# power_board.net
KiCad netlist of a schematic drawn in EAGLE
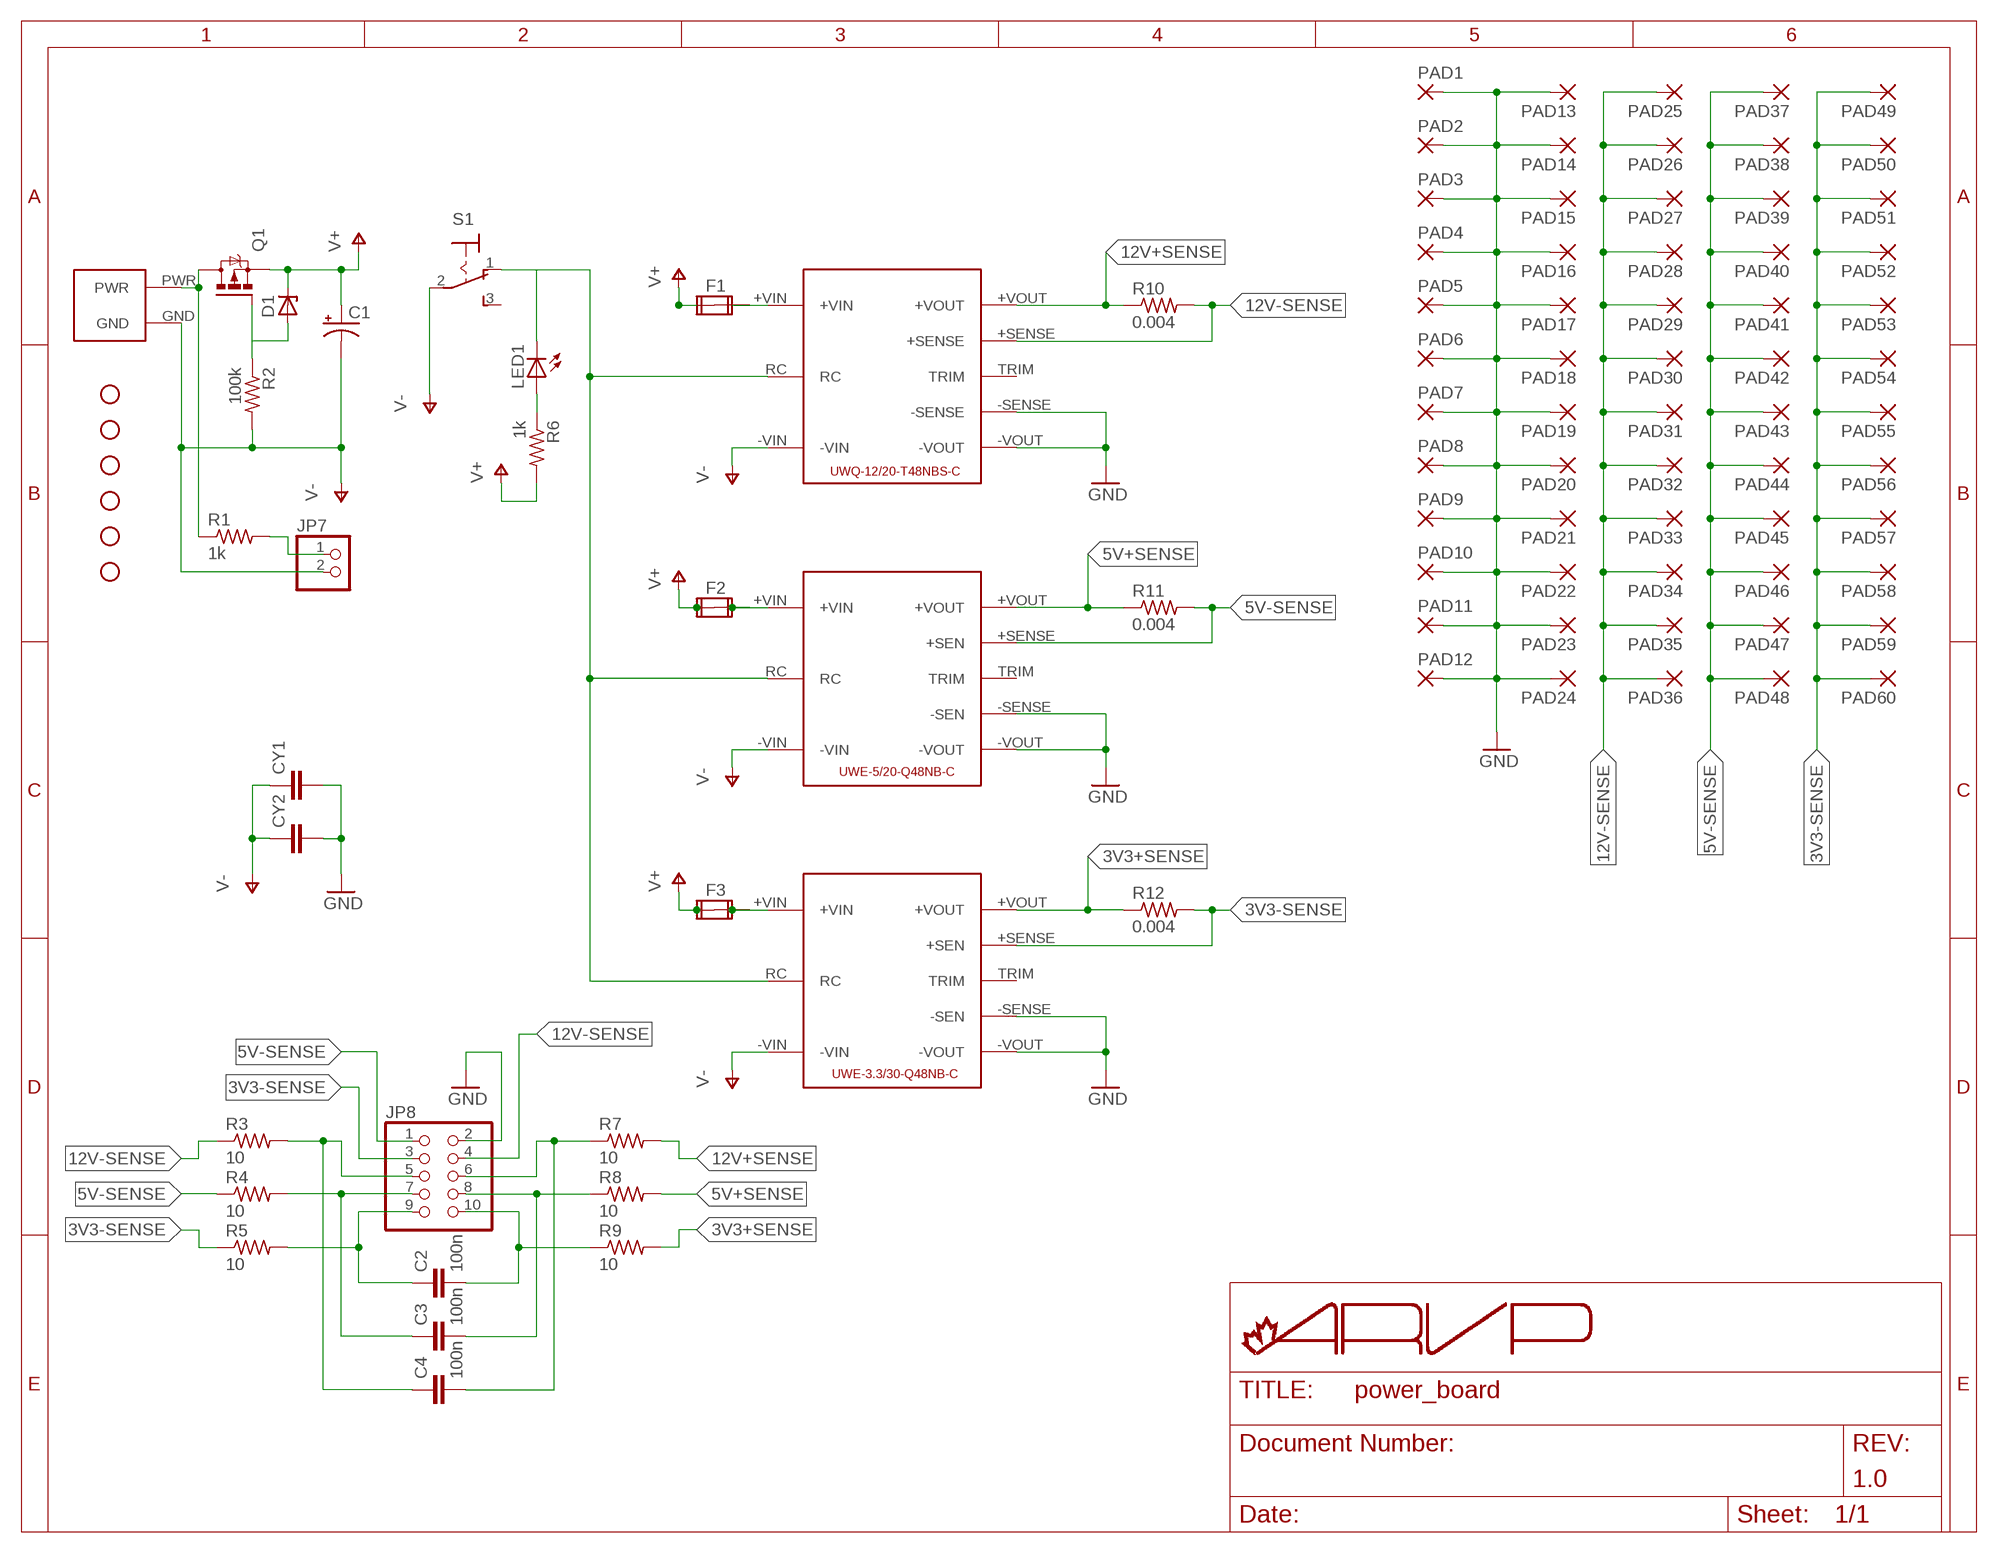
[diagram p0: schematic, sheet 1]

(export (version "E")
  (design (tool "Eeschema 10.0.6"))
  (components
    (comp (ref "C1")
      (value "CPOL-USE5-10.5")
      (footprint "eagle-import:E5-10,5")
      (libsource (lib "eagle-import") (part "CPOL-USE5-10.5"))
    )
    (comp (ref "C2")
      (value "100n")
      (footprint "eagle-import:C025-024X044")
      (libsource (lib "eagle-import") (part "C-EU025-024X044"))
    )
    (comp (ref "C3")
      (value "100n")
      (footprint "eagle-import:C025-024X044")
      (libsource (lib "eagle-import") (part "C-EU025-024X044"))
    )
    (comp (ref "C4")
      (value "100n")
      (footprint "eagle-import:C025-024X044")
      (libsource (lib "eagle-import") (part "C-EU025-024X044"))
    )
    (comp (ref "CY1")
      (value "CYYC7B5")
      (footprint "eagle-import:YC7B5")
      (libsource (lib "eagle-import") (part "CYYC7B5"))
    )
    (comp (ref "CY2")
      (value "CYYC7B5")
      (footprint "eagle-import:YC7B5")
      (libsource (lib "eagle-import") (part "CYYC7B5"))
    )
    (comp (ref "D1")
      (value "ZENER-DIODEDO35Z10")
      (footprint "eagle-import:DO35Z10")
      (libsource (lib "eagle-import") (part "ZENER-DIODEDO35Z10"))
    )
    (comp (ref "F1")
      (value "FUSE2P")
      (footprint "eagle-import:FUSE1")
      (libsource (lib "eagle-import") (part "FUSE2P"))
    )
    (comp (ref "F2")
      (value "FUSE2P")
      (footprint "eagle-import:FUSE1")
      (libsource (lib "eagle-import") (part "FUSE2P"))
    )
    (comp (ref "F3")
      (value "FUSE2P")
      (footprint "eagle-import:FUSE1")
      (libsource (lib "eagle-import") (part "FUSE2P"))
    )
    (comp (ref "JP1")
      (value "STAND-OFF")
      (footprint "eagle-import:STAND-OFF")
      (libsource (lib "eagle-import") (part "STAND-OFF"))
    )
    (comp (ref "JP2")
      (value "STAND-OFF")
      (footprint "eagle-import:STAND-OFF")
      (libsource (lib "eagle-import") (part "STAND-OFF"))
    )
    (comp (ref "JP3")
      (value "STAND-OFF")
      (footprint "eagle-import:STAND-OFF")
      (libsource (lib "eagle-import") (part "STAND-OFF"))
    )
    (comp (ref "JP4")
      (value "STAND-OFF")
      (footprint "eagle-import:STAND-OFF")
      (libsource (lib "eagle-import") (part "STAND-OFF"))
    )
    (comp (ref "JP5")
      (value "STAND-OFF")
      (footprint "eagle-import:STAND-OFF")
      (libsource (lib "eagle-import") (part "STAND-OFF"))
    )
    (comp (ref "JP6")
      (value "STAND-OFF")
      (footprint "eagle-import:STAND-OFF")
      (libsource (lib "eagle-import") (part "STAND-OFF"))
    )
    (comp (ref "JP7")
      (value "PINHD-1X2")
      (footprint "eagle-import:1X02")
      (libsource (lib "eagle-import") (part "PINHD-1X2"))
    )
    (comp (ref "JP8")
      (value "PINHD-2X5")
      (footprint "eagle-import:2X05")
      (libsource (lib "eagle-import") (part "PINHD-2X5"))
    )
    (comp (ref "LED1")
      (value "LED3MM")
      (footprint "eagle-import:LED3MM")
      (libsource (lib "eagle-import") (part "LED3MM"))
    )
    (comp (ref "P$1")
      (value "AND_PWR")
      (footprint "eagle-import:AND_PWR")
      (libsource (lib "eagle-import") (part "AND_PWR"))
    )
    (comp (ref "PAD1")
      (value "WIREPAD3,17/1,3")
      (footprint "eagle-import:3,17_1,3")
      (libsource (lib "eagle-import") (part "WIREPAD3,17/1,3"))
    )
    (comp (ref "PAD2")
      (value "WIREPAD3,17/1,3")
      (footprint "eagle-import:3,17_1,3")
      (libsource (lib "eagle-import") (part "WIREPAD3,17/1,3"))
    )
    (comp (ref "PAD3")
      (value "WIREPAD3,17/1,3")
      (footprint "eagle-import:3,17_1,3")
      (libsource (lib "eagle-import") (part "WIREPAD3,17/1,3"))
    )
    (comp (ref "PAD4")
      (value "WIREPAD3,17/1,3")
      (footprint "eagle-import:3,17_1,3")
      (libsource (lib "eagle-import") (part "WIREPAD3,17/1,3"))
    )
    (comp (ref "PAD5")
      (value "WIREPAD3,17/1,3")
      (footprint "eagle-import:3,17_1,3")
      (libsource (lib "eagle-import") (part "WIREPAD3,17/1,3"))
    )
    (comp (ref "PAD6")
      (value "WIREPAD3,17/1,3")
      (footprint "eagle-import:3,17_1,3")
      (libsource (lib "eagle-import") (part "WIREPAD3,17/1,3"))
    )
    (comp (ref "PAD7")
      (value "WIREPAD3,17/1,3")
      (footprint "eagle-import:3,17_1,3")
      (libsource (lib "eagle-import") (part "WIREPAD3,17/1,3"))
    )
    (comp (ref "PAD8")
      (value "WIREPAD3,17/1,3")
      (footprint "eagle-import:3,17_1,3")
      (libsource (lib "eagle-import") (part "WIREPAD3,17/1,3"))
    )
    (comp (ref "PAD9")
      (value "WIREPAD3,17/1,3")
      (footprint "eagle-import:3,17_1,3")
      (libsource (lib "eagle-import") (part "WIREPAD3,17/1,3"))
    )
    (comp (ref "PAD10")
      (value "WIREPAD3,17/1,3")
      (footprint "eagle-import:3,17_1,3")
      (libsource (lib "eagle-import") (part "WIREPAD3,17/1,3"))
    )
    (comp (ref "PAD11")
      (value "WIREPAD3,17/1,3")
      (footprint "eagle-import:3,17_1,3")
      (libsource (lib "eagle-import") (part "WIREPAD3,17/1,3"))
    )
    (comp (ref "PAD12")
      (value "WIREPAD3,17/1,3")
      (footprint "eagle-import:3,17_1,3")
      (libsource (lib "eagle-import") (part "WIREPAD3,17/1,3"))
    )
    (comp (ref "PAD13")
      (value "WIREPAD3,17/1,3")
      (footprint "eagle-import:3,17_1,3")
      (libsource (lib "eagle-import") (part "WIREPAD3,17/1,3"))
    )
    (comp (ref "PAD14")
      (value "WIREPAD3,17/1,3")
      (footprint "eagle-import:3,17_1,3")
      (libsource (lib "eagle-import") (part "WIREPAD3,17/1,3"))
    )
    (comp (ref "PAD15")
      (value "WIREPAD3,17/1,3")
      (footprint "eagle-import:3,17_1,3")
      (libsource (lib "eagle-import") (part "WIREPAD3,17/1,3"))
    )
    (comp (ref "PAD16")
      (value "WIREPAD3,17/1,3")
      (footprint "eagle-import:3,17_1,3")
      (libsource (lib "eagle-import") (part "WIREPAD3,17/1,3"))
    )
    (comp (ref "PAD17")
      (value "WIREPAD3,17/1,3")
      (footprint "eagle-import:3,17_1,3")
      (libsource (lib "eagle-import") (part "WIREPAD3,17/1,3"))
    )
    (comp (ref "PAD18")
      (value "WIREPAD3,17/1,3")
      (footprint "eagle-import:3,17_1,3")
      (libsource (lib "eagle-import") (part "WIREPAD3,17/1,3"))
    )
    (comp (ref "PAD19")
      (value "WIREPAD3,17/1,3")
      (footprint "eagle-import:3,17_1,3")
      (libsource (lib "eagle-import") (part "WIREPAD3,17/1,3"))
    )
    (comp (ref "PAD20")
      (value "WIREPAD3,17/1,3")
      (footprint "eagle-import:3,17_1,3")
      (libsource (lib "eagle-import") (part "WIREPAD3,17/1,3"))
    )
    (comp (ref "PAD21")
      (value "WIREPAD3,17/1,3")
      (footprint "eagle-import:3,17_1,3")
      (libsource (lib "eagle-import") (part "WIREPAD3,17/1,3"))
    )
    (comp (ref "PAD22")
      (value "WIREPAD3,17/1,3")
      (footprint "eagle-import:3,17_1,3")
      (libsource (lib "eagle-import") (part "WIREPAD3,17/1,3"))
    )
    (comp (ref "PAD23")
      (value "WIREPAD3,17/1,3")
      (footprint "eagle-import:3,17_1,3")
      (libsource (lib "eagle-import") (part "WIREPAD3,17/1,3"))
    )
    (comp (ref "PAD24")
      (value "WIREPAD3,17/1,3")
      (footprint "eagle-import:3,17_1,3")
      (libsource (lib "eagle-import") (part "WIREPAD3,17/1,3"))
    )
    (comp (ref "PAD25")
      (value "WIREPAD3,17/1,3")
      (footprint "eagle-import:3,17_1,3")
      (libsource (lib "eagle-import") (part "WIREPAD3,17/1,3"))
    )
    (comp (ref "PAD26")
      (value "WIREPAD3,17/1,3")
      (footprint "eagle-import:3,17_1,3")
      (libsource (lib "eagle-import") (part "WIREPAD3,17/1,3"))
    )
    (comp (ref "PAD27")
      (value "WIREPAD3,17/1,3")
      (footprint "eagle-import:3,17_1,3")
      (libsource (lib "eagle-import") (part "WIREPAD3,17/1,3"))
    )
    (comp (ref "PAD28")
      (value "WIREPAD3,17/1,3")
      (footprint "eagle-import:3,17_1,3")
      (libsource (lib "eagle-import") (part "WIREPAD3,17/1,3"))
    )
    (comp (ref "PAD29")
      (value "WIREPAD3,17/1,3")
      (footprint "eagle-import:3,17_1,3")
      (libsource (lib "eagle-import") (part "WIREPAD3,17/1,3"))
    )
    (comp (ref "PAD30")
      (value "WIREPAD3,17/1,3")
      (footprint "eagle-import:3,17_1,3")
      (libsource (lib "eagle-import") (part "WIREPAD3,17/1,3"))
    )
    (comp (ref "PAD31")
      (value "WIREPAD3,17/1,3")
      (footprint "eagle-import:3,17_1,3")
      (libsource (lib "eagle-import") (part "WIREPAD3,17/1,3"))
    )
    (comp (ref "PAD32")
      (value "WIREPAD3,17/1,3")
      (footprint "eagle-import:3,17_1,3")
      (libsource (lib "eagle-import") (part "WIREPAD3,17/1,3"))
    )
    (comp (ref "PAD33")
      (value "WIREPAD3,17/1,3")
      (footprint "eagle-import:3,17_1,3")
      (libsource (lib "eagle-import") (part "WIREPAD3,17/1,3"))
    )
    (comp (ref "PAD34")
      (value "WIREPAD3,17/1,3")
      (footprint "eagle-import:3,17_1,3")
      (libsource (lib "eagle-import") (part "WIREPAD3,17/1,3"))
    )
    (comp (ref "PAD35")
      (value "WIREPAD3,17/1,3")
      (footprint "eagle-import:3,17_1,3")
      (libsource (lib "eagle-import") (part "WIREPAD3,17/1,3"))
    )
    (comp (ref "PAD36")
      (value "WIREPAD3,17/1,3")
      (footprint "eagle-import:3,17_1,3")
      (libsource (lib "eagle-import") (part "WIREPAD3,17/1,3"))
    )
    (comp (ref "PAD37")
      (value "WIREPAD3,17/1,3")
      (footprint "eagle-import:3,17_1,3")
      (libsource (lib "eagle-import") (part "WIREPAD3,17/1,3"))
    )
    (comp (ref "PAD38")
      (value "WIREPAD3,17/1,3")
      (footprint "eagle-import:3,17_1,3")
      (libsource (lib "eagle-import") (part "WIREPAD3,17/1,3"))
    )
    (comp (ref "PAD39")
      (value "WIREPAD3,17/1,3")
      (footprint "eagle-import:3,17_1,3")
      (libsource (lib "eagle-import") (part "WIREPAD3,17/1,3"))
    )
    (comp (ref "PAD40")
      (value "WIREPAD3,17/1,3")
      (footprint "eagle-import:3,17_1,3")
      (libsource (lib "eagle-import") (part "WIREPAD3,17/1,3"))
    )
    (comp (ref "PAD41")
      (value "WIREPAD3,17/1,3")
      (footprint "eagle-import:3,17_1,3")
      (libsource (lib "eagle-import") (part "WIREPAD3,17/1,3"))
    )
    (comp (ref "PAD42")
      (value "WIREPAD3,17/1,3")
      (footprint "eagle-import:3,17_1,3")
      (libsource (lib "eagle-import") (part "WIREPAD3,17/1,3"))
    )
    (comp (ref "PAD43")
      (value "WIREPAD3,17/1,3")
      (footprint "eagle-import:3,17_1,3")
      (libsource (lib "eagle-import") (part "WIREPAD3,17/1,3"))
    )
    (comp (ref "PAD44")
      (value "WIREPAD3,17/1,3")
      (footprint "eagle-import:3,17_1,3")
      (libsource (lib "eagle-import") (part "WIREPAD3,17/1,3"))
    )
    (comp (ref "PAD45")
      (value "WIREPAD3,17/1,3")
      (footprint "eagle-import:3,17_1,3")
      (libsource (lib "eagle-import") (part "WIREPAD3,17/1,3"))
    )
    (comp (ref "PAD46")
      (value "WIREPAD3,17/1,3")
      (footprint "eagle-import:3,17_1,3")
      (libsource (lib "eagle-import") (part "WIREPAD3,17/1,3"))
    )
    (comp (ref "PAD47")
      (value "WIREPAD3,17/1,3")
      (footprint "eagle-import:3,17_1,3")
      (libsource (lib "eagle-import") (part "WIREPAD3,17/1,3"))
    )
    (comp (ref "PAD48")
      (value "WIREPAD3,17/1,3")
      (footprint "eagle-import:3,17_1,3")
      (libsource (lib "eagle-import") (part "WIREPAD3,17/1,3"))
    )
    (comp (ref "PAD49")
      (value "WIREPAD3,17/1,3")
      (footprint "eagle-import:3,17_1,3")
      (libsource (lib "eagle-import") (part "WIREPAD3,17/1,3"))
    )
    (comp (ref "PAD50")
      (value "WIREPAD3,17/1,3")
      (footprint "eagle-import:3,17_1,3")
      (libsource (lib "eagle-import") (part "WIREPAD3,17/1,3"))
    )
    (comp (ref "PAD51")
      (value "WIREPAD3,17/1,3")
      (footprint "eagle-import:3,17_1,3")
      (libsource (lib "eagle-import") (part "WIREPAD3,17/1,3"))
    )
    (comp (ref "PAD52")
      (value "WIREPAD3,17/1,3")
      (footprint "eagle-import:3,17_1,3")
      (libsource (lib "eagle-import") (part "WIREPAD3,17/1,3"))
    )
    (comp (ref "PAD53")
      (value "WIREPAD3,17/1,3")
      (footprint "eagle-import:3,17_1,3")
      (libsource (lib "eagle-import") (part "WIREPAD3,17/1,3"))
    )
    (comp (ref "PAD54")
      (value "WIREPAD3,17/1,3")
      (footprint "eagle-import:3,17_1,3")
      (libsource (lib "eagle-import") (part "WIREPAD3,17/1,3"))
    )
    (comp (ref "PAD55")
      (value "WIREPAD3,17/1,3")
      (footprint "eagle-import:3,17_1,3")
      (libsource (lib "eagle-import") (part "WIREPAD3,17/1,3"))
    )
    (comp (ref "PAD56")
      (value "WIREPAD3,17/1,3")
      (footprint "eagle-import:3,17_1,3")
      (libsource (lib "eagle-import") (part "WIREPAD3,17/1,3"))
    )
    (comp (ref "PAD57")
      (value "WIREPAD3,17/1,3")
      (footprint "eagle-import:3,17_1,3")
      (libsource (lib "eagle-import") (part "WIREPAD3,17/1,3"))
    )
    (comp (ref "PAD58")
      (value "WIREPAD3,17/1,3")
      (footprint "eagle-import:3,17_1,3")
      (libsource (lib "eagle-import") (part "WIREPAD3,17/1,3"))
    )
    (comp (ref "PAD59")
      (value "WIREPAD3,17/1,3")
      (footprint "eagle-import:3,17_1,3")
      (libsource (lib "eagle-import") (part "WIREPAD3,17/1,3"))
    )
    (comp (ref "PAD60")
      (value "WIREPAD3,17/1,3")
      (footprint "eagle-import:3,17_1,3")
      (libsource (lib "eagle-import") (part "WIREPAD3,17/1,3"))
    )
    (comp (ref "Q1")
      (value "IPP80P03P4L04AKSA1")
      (footprint "eagle-import:TO220BV")
      (libsource (lib "eagle-import") (part "IPP80P03P4L04AKSA1"))
    )
    (comp (ref "R1")
      (value "1k")
      (footprint "eagle-import:0204_7")
      (libsource (lib "eagle-import") (part "resistor_R-US_0204/7"))
    )
    (comp (ref "R2")
      (value "100k")
      (footprint "eagle-import:0204_7")
      (libsource (lib "eagle-import") (part "resistor_R-US_0204/7"))
    )
    (comp (ref "R3")
      (value "10")
      (footprint "eagle-import:0204_5")
      (libsource (lib "eagle-import") (part "R-US_0204/5"))
    )
    (comp (ref "R4")
      (value "10")
      (footprint "eagle-import:0204_5")
      (libsource (lib "eagle-import") (part "R-US_0204/5"))
    )
    (comp (ref "R5")
      (value "10")
      (footprint "eagle-import:0204_5")
      (libsource (lib "eagle-import") (part "R-US_0204/5"))
    )
    (comp (ref "R6")
      (value "1k")
      (footprint "eagle-import:0204_7")
      (libsource (lib "eagle-import") (part "resistor_R-US_0204/7"))
    )
    (comp (ref "R7")
      (value "10")
      (footprint "eagle-import:0204_5")
      (libsource (lib "eagle-import") (part "R-US_0204/5"))
    )
    (comp (ref "R8")
      (value "10")
      (footprint "eagle-import:0204_5")
      (libsource (lib "eagle-import") (part "R-US_0204/5"))
    )
    (comp (ref "R9")
      (value "10")
      (footprint "eagle-import:0204_5")
      (libsource (lib "eagle-import") (part "R-US_0204/5"))
    )
    (comp (ref "R10")
      (value "0.004")
      (footprint "eagle-import:0617_22")
      (libsource (lib "eagle-import") (part "R-US_0617/22"))
    )
    (comp (ref "R11")
      (value "0.004")
      (footprint "eagle-import:0617_22")
      (libsource (lib "eagle-import") (part "R-US_0617/22"))
    )
    (comp (ref "R12")
      (value "0.004")
      (footprint "eagle-import:0617_22")
      (libsource (lib "eagle-import") (part "R-US_0617/22"))
    )
    (comp (ref "S1")
      (value "M9040P")
      (footprint "eagle-import:M9040P")
      (libsource (lib "eagle-import") (part "M9040P"))
    )
    (comp (ref "U1")
      (value "UWQ-12/20-T48NBS-C")
      (footprint "eagle-import:UWQ-12_20-T48")
      (libsource (lib "eagle-import") (part "UWQ-12/20-T48NBS-C"))
    )
    (comp (ref "U2")
      (value "UWE-5/20-Q48NB-C")
      (footprint "eagle-import:UWE-100-120W")
      (libsource (lib "eagle-import") (part "UWE-5/20-Q48NB-C"))
    )
    (comp (ref "U3")
      (value "UWE-3.3/30-Q48NB-C")
      (footprint "eagle-import:UWE-100-120W")
      (libsource (lib "eagle-import") (part "UWE-3.3/30-Q48NB-C"))
    )
  )
  (nets
    (net (code "1") (name "3V3+SENSE") (class "Default")
      (node (ref "R12") (pin "1") (pinfunction "1_1") (pintype "passive"))
      (node (ref "R9") (pin "2") (pinfunction "2_2") (pintype "passive"))
      (node (ref "U3") (pin "+VOUT") (pinfunction "+VOUT_+VOUT") (pintype "power_in"))
    )
    (net (code "2") (name "3V3-SENSE") (class "Default")
      (node (ref "JP8") (pin "3") (pinfunction "3_3") (pintype "passive"))
      (node (ref "PAD49") (pin "1") (pinfunction "P_1") (pintype "passive"))
      (node (ref "PAD50") (pin "1") (pinfunction "P_1") (pintype "passive"))
      (node (ref "PAD51") (pin "1") (pinfunction "P_1") (pintype "passive"))
      (node (ref "PAD52") (pin "1") (pinfunction "P_1") (pintype "passive"))
      (node (ref "PAD53") (pin "1") (pinfunction "P_1") (pintype "passive"))
      (node (ref "PAD54") (pin "1") (pinfunction "P_1") (pintype "passive"))
      (node (ref "PAD55") (pin "1") (pinfunction "P_1") (pintype "passive"))
      (node (ref "PAD56") (pin "1") (pinfunction "P_1") (pintype "passive"))
      (node (ref "PAD57") (pin "1") (pinfunction "P_1") (pintype "passive"))
      (node (ref "PAD58") (pin "1") (pinfunction "P_1") (pintype "passive"))
      (node (ref "PAD59") (pin "1") (pinfunction "P_1") (pintype "passive"))
      (node (ref "PAD60") (pin "1") (pinfunction "P_1") (pintype "passive"))
      (node (ref "R12") (pin "2") (pinfunction "2_2") (pintype "passive"))
      (node (ref "R5") (pin "1") (pinfunction "1_1") (pintype "passive"))
      (node (ref "U3") (pin "+SENSE") (pinfunction "+SEN_+SENSE") (pintype "bidirectional"))
    )
    (net (code "3") (name "5V+SENSE") (class "Default")
      (node (ref "R11") (pin "1") (pinfunction "1_1") (pintype "passive"))
      (node (ref "R8") (pin "2") (pinfunction "2_2") (pintype "passive"))
      (node (ref "U2") (pin "+VOUT") (pinfunction "+VOUT_+VOUT") (pintype "power_in"))
    )
    (net (code "4") (name "5V-SENSE") (class "Default")
      (node (ref "JP8") (pin "1") (pinfunction "1_1") (pintype "passive"))
      (node (ref "PAD37") (pin "1") (pinfunction "P_1") (pintype "passive"))
      (node (ref "PAD38") (pin "1") (pinfunction "P_1") (pintype "passive"))
      (node (ref "PAD39") (pin "1") (pinfunction "P_1") (pintype "passive"))
      (node (ref "PAD40") (pin "1") (pinfunction "P_1") (pintype "passive"))
      (node (ref "PAD41") (pin "1") (pinfunction "P_1") (pintype "passive"))
      (node (ref "PAD42") (pin "1") (pinfunction "P_1") (pintype "passive"))
      (node (ref "PAD43") (pin "1") (pinfunction "P_1") (pintype "passive"))
      (node (ref "PAD44") (pin "1") (pinfunction "P_1") (pintype "passive"))
      (node (ref "PAD45") (pin "1") (pinfunction "P_1") (pintype "passive"))
      (node (ref "PAD46") (pin "1") (pinfunction "P_1") (pintype "passive"))
      (node (ref "PAD47") (pin "1") (pinfunction "P_1") (pintype "passive"))
      (node (ref "PAD48") (pin "1") (pinfunction "P_1") (pintype "passive"))
      (node (ref "R11") (pin "2") (pinfunction "2_2") (pintype "passive"))
      (node (ref "R4") (pin "1") (pinfunction "1_1") (pintype "passive"))
      (node (ref "U2") (pin "+SENSE") (pinfunction "+SEN_+SENSE") (pintype "bidirectional"))
    )
    (net (code "5") (name "12V+SENSE") (class "Default")
      (node (ref "R10") (pin "1") (pinfunction "1_1") (pintype "passive"))
      (node (ref "R7") (pin "2") (pinfunction "2_2") (pintype "passive"))
      (node (ref "U1") (pin "+VOUT") (pinfunction "+VOUT_+VOUT") (pintype "power_in"))
    )
    (net (code "6") (name "12V-SENSE") (class "Default")
      (node (ref "JP8") (pin "4") (pinfunction "4_4") (pintype "passive"))
      (node (ref "PAD25") (pin "1") (pinfunction "P_1") (pintype "passive"))
      (node (ref "PAD26") (pin "1") (pinfunction "P_1") (pintype "passive"))
      (node (ref "PAD27") (pin "1") (pinfunction "P_1") (pintype "passive"))
      (node (ref "PAD28") (pin "1") (pinfunction "P_1") (pintype "passive"))
      (node (ref "PAD29") (pin "1") (pinfunction "P_1") (pintype "passive"))
      (node (ref "PAD30") (pin "1") (pinfunction "P_1") (pintype "passive"))
      (node (ref "PAD31") (pin "1") (pinfunction "P_1") (pintype "passive"))
      (node (ref "PAD32") (pin "1") (pinfunction "P_1") (pintype "passive"))
      (node (ref "PAD33") (pin "1") (pinfunction "P_1") (pintype "passive"))
      (node (ref "PAD34") (pin "1") (pinfunction "P_1") (pintype "passive"))
      (node (ref "PAD35") (pin "1") (pinfunction "P_1") (pintype "passive"))
      (node (ref "PAD36") (pin "1") (pinfunction "P_1") (pintype "passive"))
      (node (ref "R10") (pin "2") (pinfunction "2_2") (pintype "passive"))
      (node (ref "R3") (pin "1") (pinfunction "1_1") (pintype "passive"))
      (node (ref "U1") (pin "+SENSE") (pinfunction "+SENSE_+SENSE") (pintype "bidirectional"))
    )
    (net (code "7") (name "GND") (class "Default")
      (node (ref "CY1") (pin "2") (pinfunction "2_2") (pintype "passive"))
      (node (ref "CY2") (pin "2") (pinfunction "2_2") (pintype "passive"))
      (node (ref "JP8") (pin "2") (pinfunction "2_2") (pintype "passive"))
      (node (ref "PAD1") (pin "1") (pinfunction "P_1") (pintype "passive"))
      (node (ref "PAD10") (pin "1") (pinfunction "P_1") (pintype "passive"))
      (node (ref "PAD11") (pin "1") (pinfunction "P_1") (pintype "passive"))
      (node (ref "PAD12") (pin "1") (pinfunction "P_1") (pintype "passive"))
      (node (ref "PAD13") (pin "1") (pinfunction "P_1") (pintype "passive"))
      (node (ref "PAD14") (pin "1") (pinfunction "P_1") (pintype "passive"))
      (node (ref "PAD15") (pin "1") (pinfunction "P_1") (pintype "passive"))
      (node (ref "PAD16") (pin "1") (pinfunction "P_1") (pintype "passive"))
      (node (ref "PAD17") (pin "1") (pinfunction "P_1") (pintype "passive"))
      (node (ref "PAD18") (pin "1") (pinfunction "P_1") (pintype "passive"))
      (node (ref "PAD19") (pin "1") (pinfunction "P_1") (pintype "passive"))
      (node (ref "PAD2") (pin "1") (pinfunction "P_1") (pintype "passive"))
      (node (ref "PAD20") (pin "1") (pinfunction "P_1") (pintype "passive"))
      (node (ref "PAD21") (pin "1") (pinfunction "P_1") (pintype "passive"))
      (node (ref "PAD22") (pin "1") (pinfunction "P_1") (pintype "passive"))
      (node (ref "PAD23") (pin "1") (pinfunction "P_1") (pintype "passive"))
      (node (ref "PAD24") (pin "1") (pinfunction "P_1") (pintype "passive"))
      (node (ref "PAD3") (pin "1") (pinfunction "P_1") (pintype "passive"))
      (node (ref "PAD4") (pin "1") (pinfunction "P_1") (pintype "passive"))
      (node (ref "PAD5") (pin "1") (pinfunction "P_1") (pintype "passive"))
      (node (ref "PAD6") (pin "1") (pinfunction "P_1") (pintype "passive"))
      (node (ref "PAD7") (pin "1") (pinfunction "P_1") (pintype "passive"))
      (node (ref "PAD8") (pin "1") (pinfunction "P_1") (pintype "passive"))
      (node (ref "PAD9") (pin "1") (pinfunction "P_1") (pintype "passive"))
      (node (ref "U1") (pin "-SENSE") (pinfunction "-SENSE_-SENSE") (pintype "bidirectional"))
      (node (ref "U1") (pin "-VOUT") (pinfunction "-VOUT_-VOUT") (pintype "power_in"))
      (node (ref "U2") (pin "-SENSE") (pinfunction "-SEN_-SENSE") (pintype "bidirectional"))
      (node (ref "U2") (pin "-VOUT") (pinfunction "-VOUT_-VOUT") (pintype "power_in"))
      (node (ref "U3") (pin "-SENSE") (pinfunction "-SEN_-SENSE") (pintype "bidirectional"))
      (node (ref "U3") (pin "-VOUT") (pinfunction "-VOUT_-VOUT") (pintype "power_in"))
    )
    (net (code "8") (name "Net-(C2-Pad1)") (class "Default")
      (node (ref "C2") (pin "1") (pinfunction "1_1") (pintype "passive"))
      (node (ref "JP8") (pin "9") (pinfunction "9_9") (pintype "passive"))
      (node (ref "R5") (pin "2") (pinfunction "2_2") (pintype "passive"))
    )
    (net (code "9") (name "Net-(C2-Pad2)") (class "Default")
      (node (ref "C2") (pin "2") (pinfunction "2_2") (pintype "passive"))
      (node (ref "JP8") (pin "10") (pinfunction "10_10") (pintype "passive"))
      (node (ref "R9") (pin "1") (pinfunction "1_1") (pintype "passive"))
    )
    (net (code "10") (name "Net-(C3-Pad1)") (class "Default")
      (node (ref "C3") (pin "1") (pinfunction "1_1") (pintype "passive"))
      (node (ref "JP8") (pin "7") (pinfunction "7_7") (pintype "passive"))
      (node (ref "R4") (pin "2") (pinfunction "2_2") (pintype "passive"))
    )
    (net (code "11") (name "Net-(C3-Pad2)") (class "Default")
      (node (ref "C3") (pin "2") (pinfunction "2_2") (pintype "passive"))
      (node (ref "JP8") (pin "8") (pinfunction "8_8") (pintype "passive"))
      (node (ref "R8") (pin "1") (pinfunction "1_1") (pintype "passive"))
    )
    (net (code "12") (name "Net-(C4-Pad1)") (class "Default")
      (node (ref "C4") (pin "1") (pinfunction "1_1") (pintype "passive"))
      (node (ref "JP8") (pin "5") (pinfunction "5_5") (pintype "passive"))
      (node (ref "R3") (pin "2") (pinfunction "2_2") (pintype "passive"))
    )
    (net (code "13") (name "Net-(C4-Pad2)") (class "Default")
      (node (ref "C4") (pin "2") (pinfunction "2_2") (pintype "passive"))
      (node (ref "JP8") (pin "6") (pinfunction "6_6") (pintype "passive"))
      (node (ref "R7") (pin "1") (pinfunction "1_1") (pintype "passive"))
    )
    (net (code "14") (name "Net-(D1-PadA)") (class "Default")
      (node (ref "D1") (pin "A") (pinfunction "A_A") (pintype "passive"))
      (node (ref "Q1") (pin "G") (pinfunction "G_G") (pintype "power_in"))
      (node (ref "R2") (pin "1") (pinfunction "1_1") (pintype "passive"))
    )
    (net (code "15") (name "Net-(F1-Pad2A)") (class "Default")
      (node (ref "F1") (pin "2A") (pinfunction "2A_2A") (pintype "passive"))
      (node (ref "F1") (pin "2B") (pinfunction "2B_2B") (pintype "passive"))
      (node (ref "U1") (pin "+VIN") (pinfunction "+VIN_+VIN") (pintype "power_in"))
    )
    (net (code "16") (name "Net-(F2-Pad2A)") (class "Default")
      (node (ref "F2") (pin "2A") (pinfunction "2A_2A") (pintype "passive"))
      (node (ref "F2") (pin "2B") (pinfunction "2B_2B") (pintype "passive"))
      (node (ref "U2") (pin "+VIN") (pinfunction "+VIN_+VIN") (pintype "power_in"))
    )
    (net (code "17") (name "Net-(F3-Pad2A)") (class "Default")
      (node (ref "F3") (pin "2A") (pinfunction "2A_2A") (pintype "passive"))
      (node (ref "F3") (pin "2B") (pinfunction "2B_2B") (pintype "passive"))
      (node (ref "U3") (pin "+VIN") (pinfunction "+VIN_+VIN") (pintype "power_in"))
    )
    (net (code "18") (name "Net-(JP7-Pad1)") (class "Default")
      (node (ref "JP7") (pin "1") (pinfunction "1_1") (pintype "passive"))
      (node (ref "R1") (pin "2") (pinfunction "2_2") (pintype "passive"))
    )
    (net (code "19") (name "Net-(LED1-C)") (class "Default")
      (node (ref "LED1") (pin "K") (pinfunction "C_K") (pintype "passive"))
      (node (ref "S1") (pin "1") (pinfunction "O_1") (pintype "passive"))
      (node (ref "U1") (pin "RC") (pinfunction "RC_RC") (pintype "bidirectional"))
      (node (ref "U2") (pin "RC") (pinfunction "RC_RC") (pintype "bidirectional"))
      (node (ref "U3") (pin "RC") (pinfunction "RC_RC") (pintype "bidirectional"))
    )
    (net (code "20") (name "Net-(LED1-PadA)") (class "Default")
      (node (ref "LED1") (pin "A") (pinfunction "A_A") (pintype "passive"))
      (node (ref "R6") (pin "1") (pinfunction "1_1") (pintype "passive"))
    )
    (net (code "21") (name "Net-(P$1-PadPWR)") (class "Default")
      (node (ref "P$1") (pin "PWR") (pinfunction "PWR_PWR") (pintype "bidirectional"))
      (node (ref "Q1") (pin "D") (pinfunction "D_D") (pintype "power_in"))
      (node (ref "R1") (pin "1") (pinfunction "1_1") (pintype "passive"))
    )
    (net (code "22") (name "V+") (class "Default")
      (node (ref "C1") (pin "+") (pinfunction "+_+") (pintype "passive"))
      (node (ref "D1") (pin "C") (pinfunction "C_C") (pintype "passive"))
      (node (ref "F1") (pin "1A") (pinfunction "1A_1A") (pintype "passive"))
      (node (ref "F1") (pin "1B") (pinfunction "1B_1B") (pintype "passive"))
      (node (ref "F2") (pin "1A") (pinfunction "1A_1A") (pintype "passive"))
      (node (ref "F2") (pin "1B") (pinfunction "1B_1B") (pintype "passive"))
      (node (ref "F3") (pin "1A") (pinfunction "1A_1A") (pintype "passive"))
      (node (ref "F3") (pin "1B") (pinfunction "1B_1B") (pintype "passive"))
      (node (ref "Q1") (pin "S") (pinfunction "S_S") (pintype "power_in"))
      (node (ref "R6") (pin "2") (pinfunction "2_2") (pintype "passive"))
    )
    (net (code "23") (name "V-") (class "Default")
      (node (ref "C1") (pin "-") (pinfunction "-_-") (pintype "passive"))
      (node (ref "CY1") (pin "1") (pinfunction "1_1") (pintype "passive"))
      (node (ref "CY2") (pin "1") (pinfunction "1_1") (pintype "passive"))
      (node (ref "JP7") (pin "2") (pinfunction "2_2") (pintype "passive"))
      (node (ref "P$1") (pin "GND") (pinfunction "GND_GND") (pintype "bidirectional"))
      (node (ref "R2") (pin "2") (pinfunction "2_2") (pintype "passive"))
      (node (ref "S1") (pin "2") (pinfunction "P_2") (pintype "passive"))
      (node (ref "U1") (pin "-VIN") (pinfunction "-VIN_-VIN") (pintype "power_in"))
      (node (ref "U2") (pin "-VIN") (pinfunction "-VIN_-VIN") (pintype "power_in"))
      (node (ref "U3") (pin "-VIN") (pinfunction "-VIN_-VIN") (pintype "power_in"))
    )
    (net (code "24") (name "unconnected-(S1-S-Pad3)") (class "Default")
      (node (ref "S1") (pin "3") (pinfunction "S_3") (pintype "passive"))
    )
    (net (code "25") (name "unconnected-(U1-PadTRIM)") (class "Default")
      (node (ref "U1") (pin "TRIM") (pinfunction "TRIM_TRIM") (pintype "bidirectional"))
    )
    (net (code "26") (name "unconnected-(U2-PadTRIM)") (class "Default")
      (node (ref "U2") (pin "TRIM") (pinfunction "TRIM_TRIM") (pintype "bidirectional"))
    )
    (net (code "27") (name "unconnected-(U3-PadTRIM)") (class "Default")
      (node (ref "U3") (pin "TRIM") (pinfunction "TRIM_TRIM") (pintype "bidirectional"))
    )
  )
)
